# Gate_Driver_Chip.net
KiCad netlist of a schematic drawn in Altium Designer
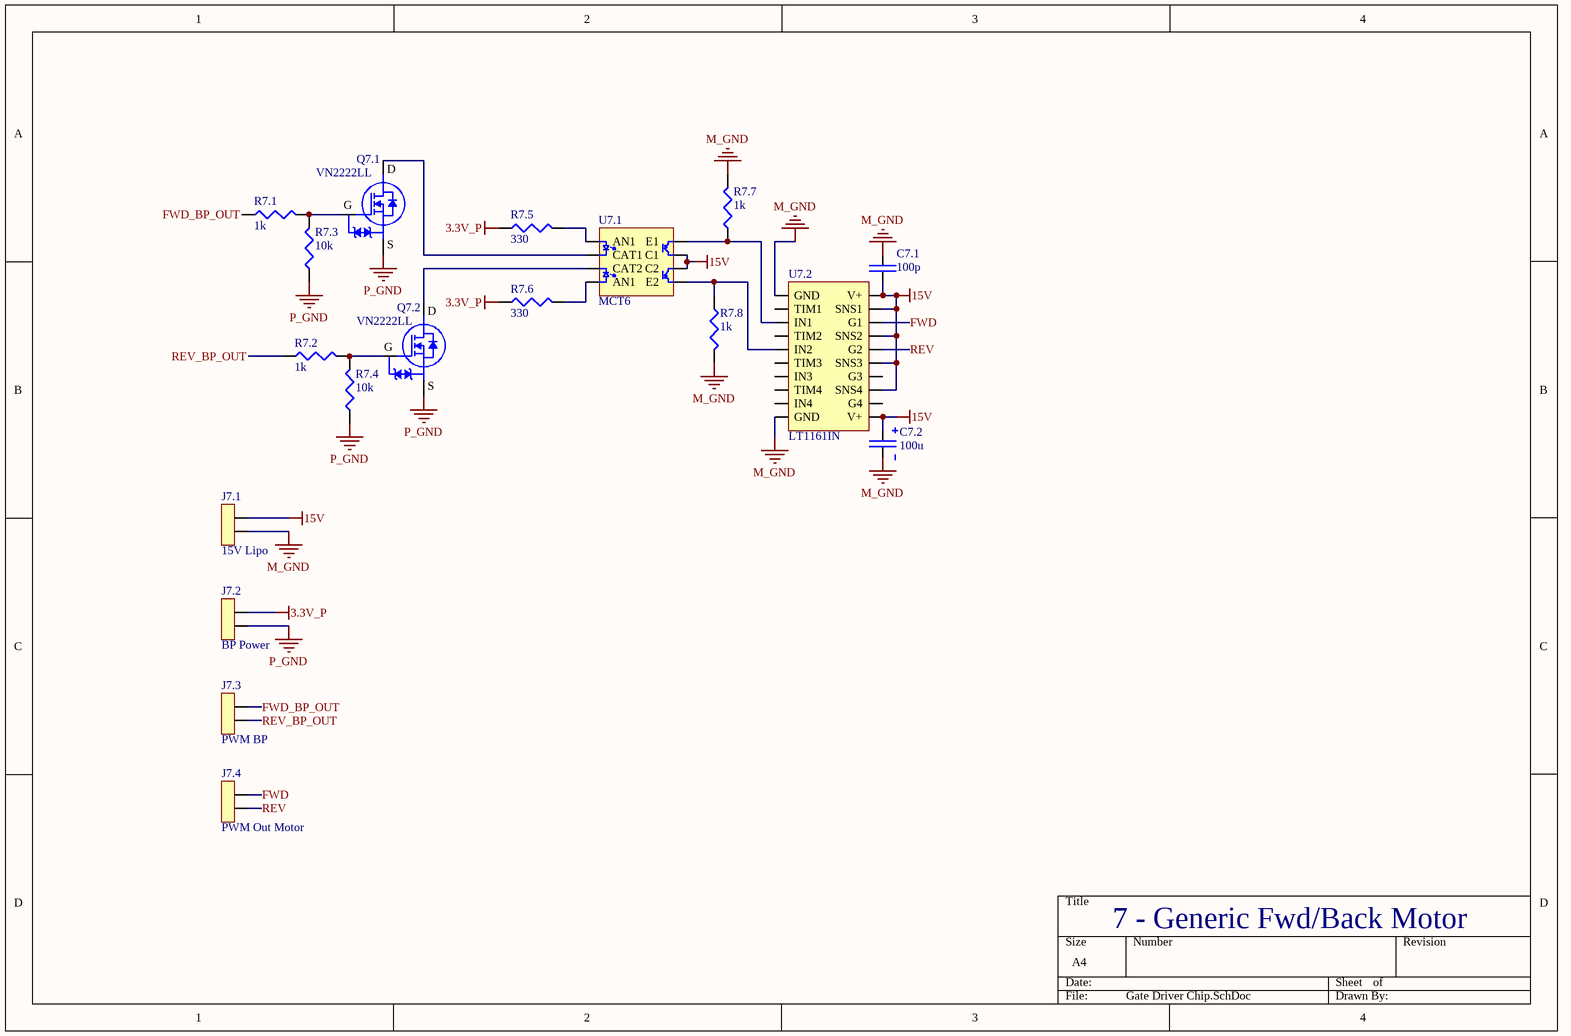
[diagram p0: Gate Driver Chip.SchDoc]

(export (version "E")
  (design (tool "Eeschema 10.0.6"))
  (components
    (comp (ref "C7.1")
      (value "100p")
      (footprint "Non Polarized Cap")
      (libsource (lib "SPICEBot_SchLib") (part "Cap_Generic"))
    )
    (comp (ref "C7.2")
      (value "100u")
      (footprint "Polarized Cap")
      (libsource (lib "SPICEBot_SchLib") (part "Polarized Cap"))
    )
    (comp (ref "J7.1")
      (value "15V Lipo")
      (footprint "2pos JST")
      (description "2pos Conn JST")
      (libsource (lib "SPICEBot_SchLib") (part "2pos Conn"))
    )
    (comp (ref "J7.2")
      (value "BP Power")
      (footprint "2pos JST")
      (description "2pos Conn JST")
      (libsource (lib "SPICEBot_SchLib") (part "2pos Conn"))
    )
    (comp (ref "J7.3")
      (value "PWM BP")
      (footprint "2pos JST")
      (description "2pos Conn JST")
      (libsource (lib "SPICEBot_SchLib") (part "2pos Conn"))
    )
    (comp (ref "J7.4")
      (value "PWM Out Motor")
      (footprint "2pos JST")
      (description "2pos Conn JST")
      (libsource (lib "SPICEBot_SchLib") (part "2pos Conn"))
    )
    (comp (ref "Q7.1")
      (value "VN2222LL")
      (footprint "VN2222LL")
      (description "VN2222LL N-Channel 60 V 150mA 400mW Through Hole TO-92 (TO-226)")
      (libsource (lib "SPICEBot_SchLib") (part "VN2222LL NMOS"))
    )
    (comp (ref "Q7.2")
      (value "VN2222LL")
      (footprint "VN2222LL")
      (description "VN2222LL N-Channel 60 V 150mA 400mW Through Hole TO-92 (TO-226)")
      (libsource (lib "SPICEBot_SchLib") (part "VN2222LL NMOS"))
    )
    (comp (ref "R7.1")
      (value "1k")
      (footprint "Res_Generic")
      (libsource (lib "SPICEBot_SchLib") (part "Res_Generic"))
    )
    (comp (ref "R7.2")
      (value "1k")
      (footprint "Res_Generic")
      (libsource (lib "SPICEBot_SchLib") (part "Res_Generic"))
    )
    (comp (ref "R7.3")
      (value "10k")
      (footprint "Res_Generic")
      (libsource (lib "SPICEBot_SchLib") (part "Res_Generic"))
    )
    (comp (ref "R7.4")
      (value "10k")
      (footprint "Res_Generic")
      (libsource (lib "SPICEBot_SchLib") (part "Res_Generic"))
    )
    (comp (ref "R7.5")
      (value "330")
      (footprint "Res_Generic")
      (libsource (lib "SPICEBot_SchLib") (part "Res_Generic"))
    )
    (comp (ref "R7.6")
      (value "330")
      (footprint "Res_Generic")
      (libsource (lib "SPICEBot_SchLib") (part "Res_Generic"))
    )
    (comp (ref "R7.7")
      (value "1k")
      (footprint "Res_Generic")
      (libsource (lib "SPICEBot_SchLib") (part "Res_Generic"))
    )
    (comp (ref "R7.8")
      (value "1k")
      (footprint "Res_Generic")
      (libsource (lib "SPICEBot_SchLib") (part "Res_Generic"))
    )
    (comp (ref "U7.1")
      (value "MCT6")
      (footprint "DIP8")
      (description "Optoisolator 5.3KV 2CH TRANS 8-DIP")
      (libsource (lib "SPICEBot_SchLib") (part "MCT6 Optocoupler"))
    )
    (comp (ref "U7.2")
      (value "LT1161IN")
      (footprint "DIP20")
      (description "LT1161IN High-Side Gate Driver IC Non-Inverting 20-PDIP")
      (libsource (lib "SPICEBot_SchLib") (part "LT1161IN Gate Driver"))
    )
  )
  (nets
    (net (code "1") (name "/FWD") (class "Default")
      (node (ref "J7.4") (pin "2") (pinfunction "2_2") (pintype "passive"))
      (node (ref "U7.2") (pin "18") (pinfunction "G1_18") (pintype "passive"))
    )
    (net (code "2") (name "/FWD_BP_OUT") (class "Default")
      (node (ref "J7.3") (pin "2") (pinfunction "2_2") (pintype "passive"))
      (node (ref "R7.1") (pin "1") (pinfunction "1_1") (pintype "passive"))
    )
    (net (code "3") (name "/REV") (class "Default")
      (node (ref "J7.4") (pin "1") (pinfunction "1_1") (pintype "passive"))
      (node (ref "U7.2") (pin "16") (pinfunction "G2_16") (pintype "passive"))
    )
    (net (code "4") (name "/REV_BP_OUT") (class "Default")
      (node (ref "J7.3") (pin "1") (pinfunction "1_1") (pintype "passive"))
      (node (ref "R7.2") (pin "1") (pinfunction "1_1") (pintype "passive"))
    )
    (net (code "5") (name "3.3V_P") (class "Default")
      (node (ref "J7.2") (pin "2") (pinfunction "2_2") (pintype "passive"))
      (node (ref "R7.5") (pin "1") (pinfunction "1_1") (pintype "passive"))
      (node (ref "R7.6") (pin "1") (pinfunction "1_1") (pintype "passive"))
    )
    (net (code "6") (name "15V") (class "Default")
      (node (ref "C7.1") (pin "1") (pinfunction "1_1") (pintype "passive"))
      (node (ref "C7.2") (pin "1") (pinfunction "1_1") (pintype "passive"))
      (node (ref "J7.1") (pin "2") (pinfunction "2_2") (pintype "passive"))
      (node (ref "U7.1") (pin "6") (pinfunction "C2_6") (pintype "passive"))
      (node (ref "U7.1") (pin "7") (pinfunction "C1_7") (pintype "passive"))
      (node (ref "U7.2") (pin "11") (pinfunction "V+_11") (pintype "passive"))
      (node (ref "U7.2") (pin "13") (pinfunction "SNS4_13") (pintype "passive"))
      (node (ref "U7.2") (pin "15") (pinfunction "SNS3_15") (pintype "passive"))
      (node (ref "U7.2") (pin "17") (pinfunction "SNS2_17") (pintype "passive"))
      (node (ref "U7.2") (pin "19") (pinfunction "SNS1_19") (pintype "passive"))
      (node (ref "U7.2") (pin "20") (pinfunction "V+_20") (pintype "passive"))
    )
    (net (code "7") (name "M_GND") (class "Default")
      (node (ref "C7.1") (pin "2") (pinfunction "2_2") (pintype "passive"))
      (node (ref "C7.2") (pin "2") (pinfunction "2_2") (pintype "passive"))
      (node (ref "J7.1") (pin "1") (pinfunction "1_1") (pintype "passive"))
      (node (ref "R7.7") (pin "2") (pinfunction "2_2") (pintype "passive"))
      (node (ref "R7.8") (pin "2") (pinfunction "2_2") (pintype "passive"))
      (node (ref "U7.2") (pin "1") (pinfunction "GND_1") (pintype "passive"))
      (node (ref "U7.2") (pin "10") (pinfunction "GND_10") (pintype "passive"))
    )
    (net (code "8") (name "Net-(Q7.1-D)") (class "Default")
      (node (ref "Q7.1") (pin "3") (pinfunction "D_3") (pintype "passive"))
      (node (ref "U7.1") (pin "2") (pinfunction "CAT1_2") (pintype "passive"))
    )
    (net (code "9") (name "Net-(Q7.1-G)") (class "Default")
      (node (ref "Q7.1") (pin "2") (pinfunction "G_2") (pintype "passive"))
      (node (ref "R7.1") (pin "2") (pinfunction "2_2") (pintype "passive"))
      (node (ref "R7.3") (pin "2") (pinfunction "2_2") (pintype "passive"))
    )
    (net (code "10") (name "Net-(Q7.2-D)") (class "Default")
      (node (ref "Q7.2") (pin "3") (pinfunction "D_3") (pintype "passive"))
      (node (ref "U7.1") (pin "3") (pinfunction "CAT2_3") (pintype "passive"))
    )
    (net (code "11") (name "Net-(Q7.2-G)") (class "Default")
      (node (ref "Q7.2") (pin "2") (pinfunction "G_2") (pintype "passive"))
      (node (ref "R7.2") (pin "2") (pinfunction "2_2") (pintype "passive"))
      (node (ref "R7.4") (pin "2") (pinfunction "2_2") (pintype "passive"))
    )
    (net (code "12") (name "Net-(R7.5-Pad2)") (class "Default")
      (node (ref "R7.5") (pin "2") (pinfunction "2_2") (pintype "passive"))
      (node (ref "U7.1") (pin "1") (pinfunction "AN1_1") (pintype "passive"))
    )
    (net (code "13") (name "Net-(R7.6-Pad2)") (class "Default")
      (node (ref "R7.6") (pin "2") (pinfunction "2_2") (pintype "passive"))
      (node (ref "U7.1") (pin "4") (pinfunction "AN1_4") (pintype "passive"))
    )
    (net (code "14") (name "Net-(U7.1-E1)") (class "Default")
      (node (ref "R7.7") (pin "1") (pinfunction "1_1") (pintype "passive"))
      (node (ref "U7.1") (pin "8") (pinfunction "E1_8") (pintype "passive"))
      (node (ref "U7.2") (pin "3") (pinfunction "IN1_3") (pintype "passive"))
    )
    (net (code "15") (name "Net-(U7.1-E2)") (class "Default")
      (node (ref "R7.8") (pin "1") (pinfunction "1_1") (pintype "passive"))
      (node (ref "U7.1") (pin "5") (pinfunction "E2_5") (pintype "passive"))
      (node (ref "U7.2") (pin "5") (pinfunction "IN2_5") (pintype "passive"))
    )
    (net (code "16") (name "P_GND") (class "Default")
      (node (ref "J7.2") (pin "1") (pinfunction "1_1") (pintype "passive"))
      (node (ref "Q7.1") (pin "1") (pinfunction "S_1") (pintype "passive"))
      (node (ref "Q7.2") (pin "1") (pinfunction "S_1") (pintype "passive"))
      (node (ref "R7.3") (pin "1") (pinfunction "1_1") (pintype "passive"))
      (node (ref "R7.4") (pin "1") (pinfunction "1_1") (pintype "passive"))
    )
    (net (code "17") (name "unconnected-(U7.2-G3-Pad14)") (class "Default")
      (node (ref "U7.2") (pin "14") (pinfunction "G3_14") (pintype "passive"))
    )
    (net (code "18") (name "unconnected-(U7.2-G4-Pad12)") (class "Default")
      (node (ref "U7.2") (pin "12") (pinfunction "G4_12") (pintype "passive"))
    )
    (net (code "19") (name "unconnected-(U7.2-IN3-Pad7)") (class "Default")
      (node (ref "U7.2") (pin "7") (pinfunction "IN3_7") (pintype "passive"))
    )
    (net (code "20") (name "unconnected-(U7.2-IN4-Pad9)") (class "Default")
      (node (ref "U7.2") (pin "9") (pinfunction "IN4_9") (pintype "passive"))
    )
    (net (code "21") (name "unconnected-(U7.2-TIM1-Pad2)") (class "Default")
      (node (ref "U7.2") (pin "2") (pinfunction "TIM1_2") (pintype "passive"))
    )
    (net (code "22") (name "unconnected-(U7.2-TIM2-Pad4)") (class "Default")
      (node (ref "U7.2") (pin "4") (pinfunction "TIM2_4") (pintype "passive"))
    )
    (net (code "23") (name "unconnected-(U7.2-TIM3-Pad6)") (class "Default")
      (node (ref "U7.2") (pin "6") (pinfunction "TIM3_6") (pintype "passive"))
    )
    (net (code "24") (name "unconnected-(U7.2-TIM4-Pad8)") (class "Default")
      (node (ref "U7.2") (pin "8") (pinfunction "TIM4_8") (pintype "passive"))
    )
  )
)
